# grove_pi.net
KiCad netlist of a schematic drawn in EAGLE
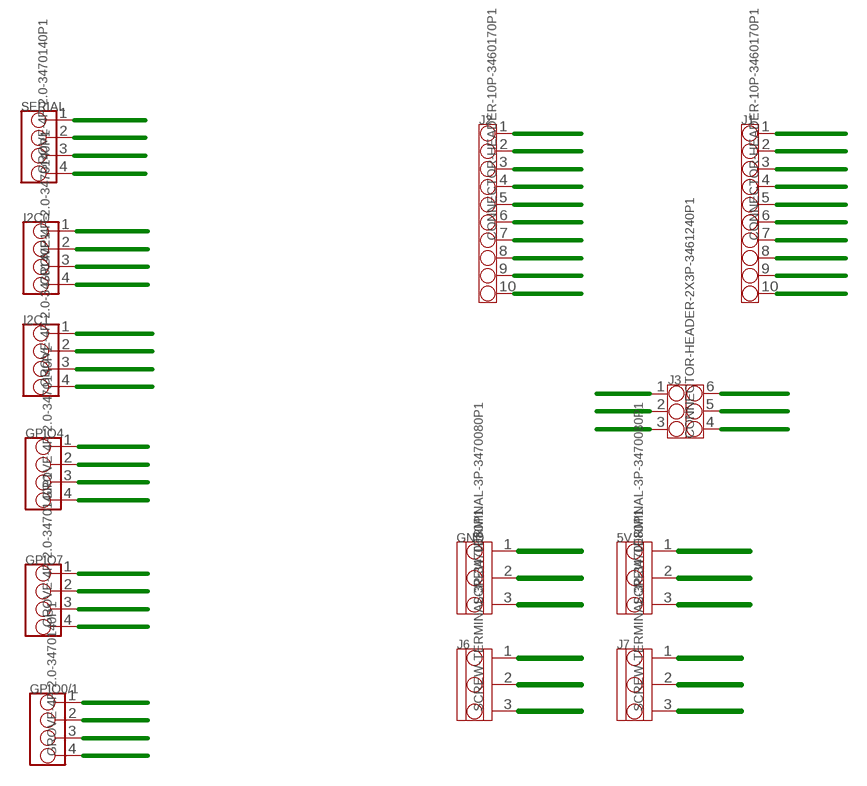
[diagram p0: schematic, sheet 1]

(export (version "E")
  (design (tool "Eeschema 10.0.6"))
  (components
    (comp (ref "5V")
      (value "SCREW-TERMINAL-3P-3470080P1")
      (footprint "eagle-import:3P-5.0")
      (libsource (lib "eagle-import") (part "SCREW-TERMINAL-3P-3470080P1"))
    )
    (comp (ref "GND")
      (value "SCREW-TERMINAL-3P-3470080P1")
      (footprint "eagle-import:3P-5.0")
      (libsource (lib "eagle-import") (part "SCREW-TERMINAL-3P-3470080P1"))
    )
    (comp (ref "GPIO0/1")
      (value "GROVE-4P-2.0-3470140P1")
      (footprint "eagle-import:4P-2.0-90D")
      (libsource (lib "eagle-import") (part "GROVE-4P-2.0-3470140P1"))
    )
    (comp (ref "GPIO4")
      (value "GROVE-4P-2.0-3470140P1")
      (footprint "eagle-import:4P-2.0-90D")
      (libsource (lib "eagle-import") (part "GROVE-4P-2.0-3470140P1"))
    )
    (comp (ref "GPIO7")
      (value "GROVE-4P-2.0-3470140P1")
      (footprint "eagle-import:4P-2.0-90D")
      (libsource (lib "eagle-import") (part "GROVE-4P-2.0-3470140P1"))
    )
    (comp (ref "I2C0")
      (value "GROVE-4P-2.0-3470140P1")
      (footprint "eagle-import:4P-2.0-90D")
      (libsource (lib "eagle-import") (part "GROVE-4P-2.0-3470140P1"))
    )
    (comp (ref "I2C1")
      (value "GROVE-4P-2.0-3470140P1")
      (footprint "eagle-import:4P-2.0-90D")
      (libsource (lib "eagle-import") (part "GROVE-4P-2.0-3470140P1"))
    )
    (comp (ref "J1")
      (value "CONNECTOR-HEADER-10P-3460170P1")
      (footprint "eagle-import:1X10P-2.54-8.5-YELLOW-FEMALE")
      (libsource (lib "eagle-import") (part "CONNECTOR-HEADER-10P-3460170P1"))
    )
    (comp (ref "J2")
      (value "CONNECTOR-HEADER-10P-3460170P1")
      (footprint "eagle-import:1X10P-2.54-8.5-YELLOW-FEMALE")
      (libsource (lib "eagle-import") (part "CONNECTOR-HEADER-10P-3460170P1"))
    )
    (comp (ref "J3")
      (value "CONNECTOR-HEADER-2X3P-3461240P1")
      (footprint "eagle-import:2X3P-2.54-8.5+1.5-12.3-BLUE-FEMALE")
      (libsource (lib "eagle-import") (part "CONNECTOR-HEADER-2X3P-3461240P1"))
    )
    (comp (ref "J6")
      (value "SCREW-TERMINAL-3P-3470080P1")
      (footprint "eagle-import:3P-5.0")
      (libsource (lib "eagle-import") (part "SCREW-TERMINAL-3P-3470080P1"))
    )
    (comp (ref "J7")
      (value "SCREW-TERMINAL-3P-3470080P1")
      (footprint "eagle-import:3P-5.0")
      (libsource (lib "eagle-import") (part "SCREW-TERMINAL-3P-3470080P1"))
    )
    (comp (ref "SERIAL")
      (value "GROVE-4P-2.0-3470140P1")
      (footprint "eagle-import:4P-2.0-90D")
      (libsource (lib "eagle-import") (part "GROVE-4P-2.0-3470140P1"))
    )
  )
  (nets
    (net (code "1") (name "/3V3") (class "Default")
      (node (ref "J1") (pin "1") (pinfunction "1_1") (pintype "bidirectional"))
    )
    (net (code "2") (name "/5V") (class "Default")
      (node (ref "5V") (pin "1") (pinfunction "P$1_1") (pintype "bidirectional"))
      (node (ref "5V") (pin "2") (pinfunction "P$2_2") (pintype "bidirectional"))
      (node (ref "5V") (pin "3") (pinfunction "P$3_3") (pintype "bidirectional"))
      (node (ref "GPIO0/1") (pin "3") (pinfunction "3_3") (pintype "bidirectional"))
      (node (ref "GPIO4") (pin "3") (pinfunction "3_3") (pintype "bidirectional"))
      (node (ref "GPIO7") (pin "3") (pinfunction "3_3") (pintype "bidirectional"))
      (node (ref "I2C0") (pin "3") (pinfunction "3_3") (pintype "bidirectional"))
      (node (ref "I2C1") (pin "3") (pinfunction "3_3") (pintype "bidirectional"))
      (node (ref "J2") (pin "1") (pinfunction "1_1") (pintype "bidirectional"))
      (node (ref "SERIAL") (pin "3") (pinfunction "3_3") (pintype "bidirectional"))
    )
    (net (code "3") (name "/CE0(SPI)") (class "Default")
      (node (ref "J3") (pin "5") (pinfunction "5_5") (pintype "bidirectional"))
    )
    (net (code "4") (name "/CE1(SPI)") (class "Default")
      (node (ref "J3") (pin "4") (pinfunction "4_4") (pintype "bidirectional"))
    )
    (net (code "5") (name "/DNC") (class "Default")
      (node (ref "J2") (pin "2") (pinfunction "2_2") (pintype "bidirectional"))
    )
    (net (code "6") (name "/DNC1") (class "Default")
      (node (ref "J1") (pin "5") (pinfunction "5_5") (pintype "bidirectional"))
    )
    (net (code "7") (name "/DNC2") (class "Default")
      (node (ref "J2") (pin "7") (pinfunction "7_7") (pintype "bidirectional"))
    )
    (net (code "8") (name "/DNC3") (class "Default")
      (node (ref "J2") (pin "10") (pinfunction "10_10") (pintype "bidirectional"))
    )
    (net (code "9") (name "/DNC4") (class "Default")
      (node (ref "J1") (pin "9") (pinfunction "9_9") (pintype "bidirectional"))
    )
    (net (code "10") (name "/DNC5") (class "Default")
      (node (ref "J3") (pin "3") (pinfunction "3_3") (pintype "bidirectional"))
    )
    (net (code "11") (name "/GND") (class "Default")
      (node (ref "GND") (pin "1") (pinfunction "P$1_1") (pintype "bidirectional"))
      (node (ref "GND") (pin "2") (pinfunction "P$2_2") (pintype "bidirectional"))
      (node (ref "GND") (pin "3") (pinfunction "P$3_3") (pintype "bidirectional"))
      (node (ref "GPIO0/1") (pin "4") (pinfunction "4_4") (pintype "bidirectional"))
      (node (ref "GPIO4") (pin "4") (pinfunction "4_4") (pintype "bidirectional"))
      (node (ref "GPIO7") (pin "4") (pinfunction "4_4") (pintype "bidirectional"))
      (node (ref "I2C0") (pin "4") (pinfunction "4_4") (pintype "bidirectional"))
      (node (ref "I2C1") (pin "4") (pinfunction "4_4") (pintype "bidirectional"))
      (node (ref "J2") (pin "3") (pinfunction "3_3") (pintype "bidirectional"))
      (node (ref "SERIAL") (pin "4") (pinfunction "4_4") (pintype "bidirectional"))
    )
    (net (code "12") (name "/GPIO0") (class "Default")
      (node (ref "GPIO0/1") (pin "1") (pinfunction "1_1") (pintype "bidirectional"))
      (node (ref "J1") (pin "6") (pinfunction "6_6") (pintype "bidirectional"))
    )
    (net (code "13") (name "/GPIO1") (class "Default")
      (node (ref "GPIO0/1") (pin "2") (pinfunction "2_2") (pintype "bidirectional"))
      (node (ref "J2") (pin "6") (pinfunction "6_6") (pintype "bidirectional"))
      (node (ref "J6") (pin "1") (pinfunction "P$1_1") (pintype "bidirectional"))
    )
    (net (code "14") (name "/GPIO2") (class "Default")
      (node (ref "J1") (pin "7") (pinfunction "7_7") (pintype "bidirectional"))
      (node (ref "J6") (pin "2") (pinfunction "P$2_2") (pintype "bidirectional"))
    )
    (net (code "15") (name "/GPIO3") (class "Default")
      (node (ref "J1") (pin "8") (pinfunction "8_8") (pintype "bidirectional"))
      (node (ref "J6") (pin "3") (pinfunction "P$3_3") (pintype "bidirectional"))
    )
    (net (code "16") (name "/GPIO4") (class "Default")
      (node (ref "GPIO4") (pin "1") (pinfunction "1_1") (pintype "bidirectional"))
      (node (ref "GPIO4") (pin "2") (pinfunction "2_2") (pintype "bidirectional"))
      (node (ref "J2") (pin "8") (pinfunction "8_8") (pintype "bidirectional"))
      (node (ref "J7") (pin "1") (pinfunction "P$1_1") (pintype "bidirectional"))
    )
    (net (code "17") (name "/GPIO5") (class "Default")
      (node (ref "J2") (pin "9") (pinfunction "9_9") (pintype "bidirectional"))
      (node (ref "J7") (pin "2") (pinfunction "P$2_2") (pintype "bidirectional"))
    )
    (net (code "18") (name "/GPIO6") (class "Default")
      (node (ref "J3") (pin "6") (pinfunction "6_6") (pintype "bidirectional"))
      (node (ref "J7") (pin "3") (pinfunction "P$3_3") (pintype "bidirectional"))
    )
    (net (code "19") (name "/GPIO7") (class "Default")
      (node (ref "GPIO7") (pin "1") (pinfunction "1_1") (pintype "bidirectional"))
      (node (ref "GPIO7") (pin "2") (pinfunction "2_2") (pintype "bidirectional"))
      (node (ref "J1") (pin "4") (pinfunction "4_4") (pintype "bidirectional"))
    )
    (net (code "20") (name "/MISO(SPI)") (class "Default")
      (node (ref "J3") (pin "1") (pinfunction "1_1") (pintype "bidirectional"))
    )
    (net (code "21") (name "/MOSI(SPI)") (class "Default")
      (node (ref "J1") (pin "10") (pinfunction "10_10") (pintype "bidirectional"))
    )
    (net (code "22") (name "/RXD") (class "Default")
      (node (ref "J2") (pin "5") (pinfunction "5_5") (pintype "bidirectional"))
      (node (ref "SERIAL") (pin "1") (pinfunction "1_1") (pintype "bidirectional"))
    )
    (net (code "23") (name "/SCL0(I2C)") (class "Default")
      (node (ref "I2C0") (pin "1") (pinfunction "1_1") (pintype "bidirectional"))
      (node (ref "I2C1") (pin "1") (pinfunction "1_1") (pintype "bidirectional"))
      (node (ref "J1") (pin "3") (pinfunction "3_3") (pintype "bidirectional"))
    )
    (net (code "24") (name "/SCLK(SPI)") (class "Default")
      (node (ref "J3") (pin "2") (pinfunction "2_2") (pintype "bidirectional"))
    )
    (net (code "25") (name "/SDA0(I2C)") (class "Default")
      (node (ref "I2C0") (pin "2") (pinfunction "2_2") (pintype "bidirectional"))
      (node (ref "I2C1") (pin "2") (pinfunction "2_2") (pintype "bidirectional"))
      (node (ref "J1") (pin "2") (pinfunction "2_2") (pintype "bidirectional"))
    )
    (net (code "26") (name "/TXD") (class "Default")
      (node (ref "J2") (pin "4") (pinfunction "4_4") (pintype "bidirectional"))
      (node (ref "SERIAL") (pin "2") (pinfunction "2_2") (pintype "bidirectional"))
    )
  )
)
